# Uc_Ticketing_Slave.net
KiCad netlist of a schematic drawn in Altium Designer
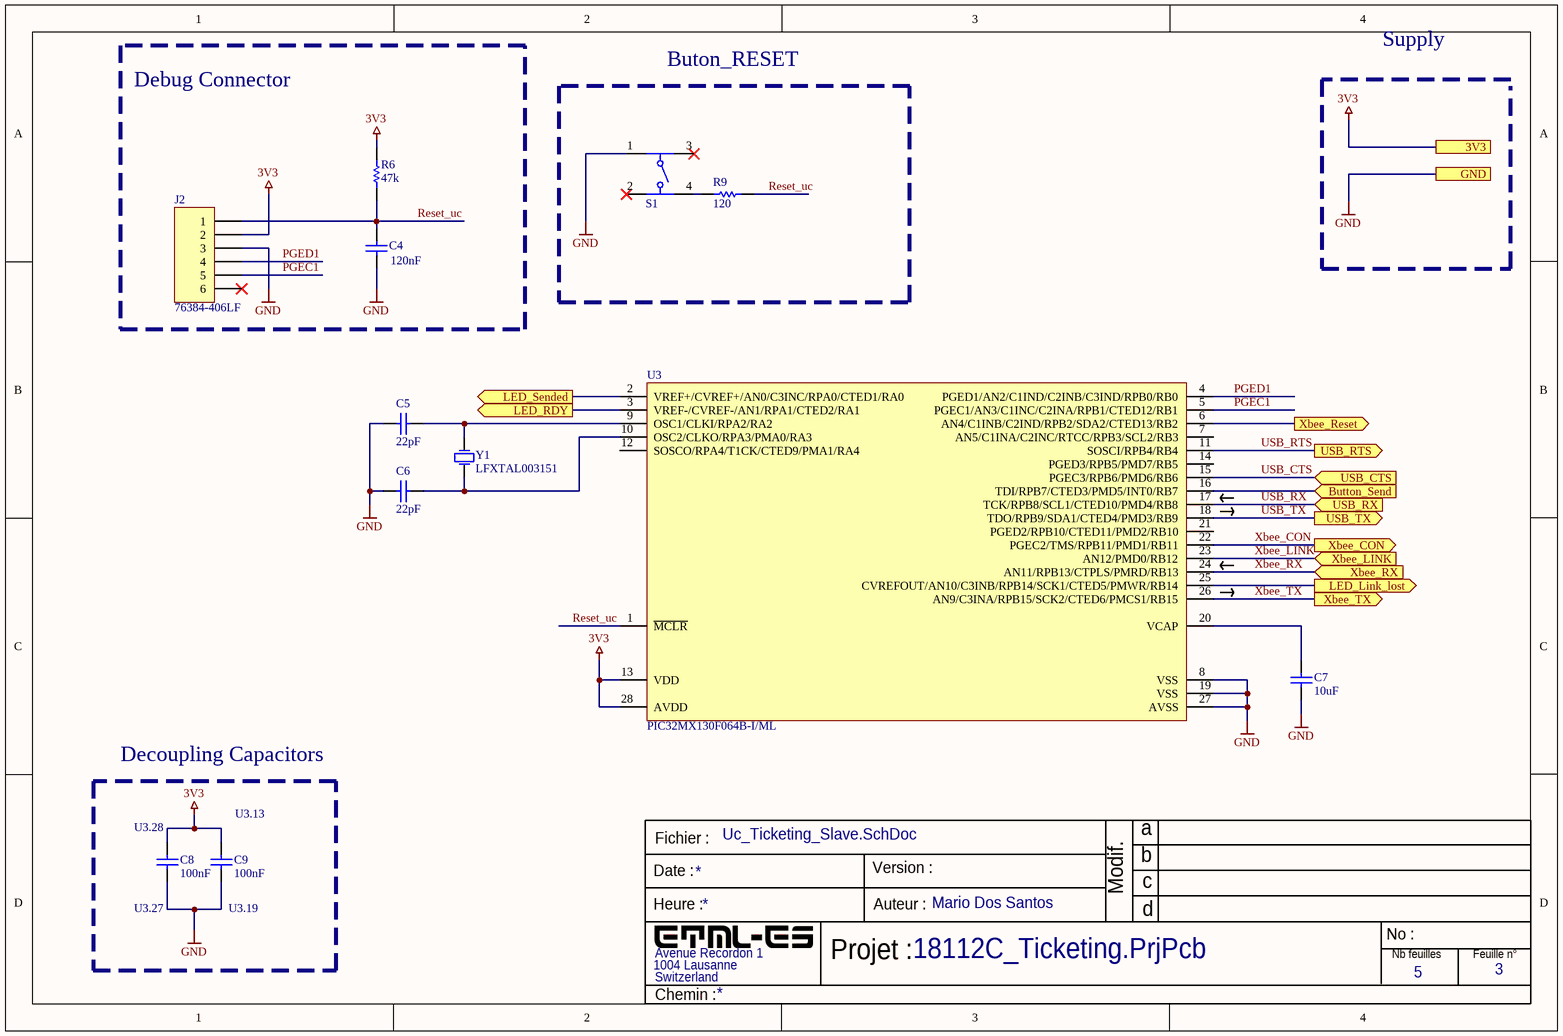
[diagram p0: Uc_Ticketing_Slave.SchDoc]

(export (version "E")
  (design (tool "Eeschema 10.0.6"))
  (components
    (comp (ref "C4")
      (value "120nF")
      (footprint "6-0805_N")
      (description "Capacitor")
      (libsource (lib "Miscellaneous Devices") (part "Cap"))
    )
    (comp (ref "C5")
      (value "22pF")
      (footprint "6-0805_N")
      (description "VJ0805Y104KNAAT")
      (libsource (lib "2126_AffichageMatriciel") (part "CMP-2007-03167-1"))
    )
    (comp (ref "C6")
      (value "22pF")
      (footprint "6-0805_N")
      (description "VJ0805Y104KNAAT")
      (libsource (lib "2126_AffichageMatriciel") (part "CMP-2007-03167-1"))
    )
    (comp (ref "C7")
      (value "10uF")
      (footprint "6-0805_N")
      (description "Capacitor")
      (libsource (lib "Miscellaneous Devices") (part "Cap"))
    )
    (comp (ref "C8")
      (value "100nF")
      (footprint "6-0805_N")
      (description "Capacitor")
      (libsource (lib "Miscellaneous Devices") (part "Cap"))
    )
    (comp (ref "C9")
      (value "100nF")
      (footprint "6-0805_N")
      (description "Capacitor")
      (libsource (lib "Miscellaneous Devices") (part "Cap"))
    )
    (comp (ref "J2")
      (value "76384-406LF")
      (footprint "76384-406LF")
      (description "Header, 6-Pin")
      (fields (field (name "PUBLISHER") "Altium Limited"))
      (libsource (lib "Miscellaneous Connectors") (part "Header 6"))
    )
    (comp (ref "R6")
      (value "47k")
      (footprint "RESC0805(2012)_L")
      (description "100K 0.125W 5% 0805 (2012 Metric)  SMD")
      (libsource (lib "Altium Content Vault") (part "CMP-1013-00122-1"))
    )
    (comp (ref "R9")
      (value "120")
      (footprint "RESC0805(2012)_L")
      (description "100K 0.125W 5% 0805 (2012 Metric)  SMD")
      (libsource (lib "Altium Content Vault") (part "CMP-1013-00122-1"))
    )
    (comp (ref "S1")
      (value "430182050816")
      (footprint "430182050816")
      (description "6x6mm SMD Tact Switch WS-TASV, height 5 mm, 160 gf")
      (libsource (lib "ALTIUM-WS-TASV-rev17b") (part "430182050816"))
    )
    (comp (ref "U3")
      (value "PIC32MX130F064B-I/ML")
      (footprint "SOP65P780X200-28N")
      (libsource (lib "PCB_Ticketing_Slave") (part "CMP-0048-00437-1"))
    )
    (comp (ref "Y1")
      (value "LFXTAL003151")
      (footprint "LFXTAL003151REEL")
      (description "Crystal or Oscillator")
      (libsource (lib "2126_AffichageMatriciel") (part "LFXTAL003151REEL"))
    )
  )
  (nets
    (net (code "1") (name "/Button_Send") (class "Default")
      (node (ref "U3") (pin "16") (pinfunction "TDI/RPB7/CTED3/PMD5/INT0/RB7_16") (pintype "passive"))
    )
    (net (code "2") (name "/LED_Link_lost") (class "Default")
      (node (ref "U3") (pin "25") (pinfunction "CVREFOUT/AN10/C3INB/RPB14/SCK1/CTED5/PMWR/RB14_25") (pintype "passive"))
    )
    (net (code "3") (name "/LED_RDY") (class "Default")
      (node (ref "U3") (pin "3") (pinfunction "VREF-/CVREF-/AN1/RPA1/CTED2/RA1_3") (pintype "passive"))
    )
    (net (code "4") (name "/LED_Sended") (class "Default")
      (node (ref "U3") (pin "2") (pinfunction "VREF+/CVREF+/AN0/C3INC/RPA0/CTED1/RA0_2") (pintype "passive"))
    )
    (net (code "5") (name "/PGEC1") (class "Default")
      (node (ref "J2") (pin "5") (pinfunction "5_5") (pintype "passive"))
      (node (ref "U3") (pin "5") (pinfunction "PGEC1/AN3/C1INC/C2INA/RPB1/CTED12/RB1_5") (pintype "passive"))
    )
    (net (code "6") (name "/PGED1") (class "Default")
      (node (ref "J2") (pin "4") (pinfunction "4_4") (pintype "passive"))
      (node (ref "U3") (pin "4") (pinfunction "PGED1/AN2/C1IND/C2INB/C3IND/RPB0/RB0_4") (pintype "passive"))
    )
    (net (code "7") (name "/Reset_uc") (class "Default")
      (node (ref "C4") (pin "2") (pinfunction "2_2") (pintype "passive"))
      (node (ref "J2") (pin "1") (pinfunction "1_1") (pintype "passive"))
      (node (ref "R6") (pin "2") (pinfunction "2_2") (pintype "passive"))
      (node (ref "R9") (pin "2") (pinfunction "2_2") (pintype "passive"))
      (node (ref "U3") (pin "1") (pinfunction "~{MCLR}_1") (pintype "passive"))
    )
    (net (code "8") (name "/USB_CTS") (class "Default")
      (node (ref "U3") (pin "15") (pinfunction "PGEC3/RPB6/PMD6/RB6_15") (pintype "passive"))
    )
    (net (code "9") (name "/USB_RTS") (class "Default")
      (node (ref "U3") (pin "11") (pinfunction "SOSCI/RPB4/RB4_11") (pintype "passive"))
    )
    (net (code "10") (name "/USB_RX") (class "Default")
      (node (ref "U3") (pin "17") (pinfunction "TCK/RPB8/SCL1/CTED10/PMD4/RB8_17") (pintype "passive"))
    )
    (net (code "11") (name "/USB_TX") (class "Default")
      (node (ref "U3") (pin "18") (pinfunction "TDO/RPB9/SDA1/CTED4/PMD3/RB9_18") (pintype "passive"))
    )
    (net (code "12") (name "/Xbee_CON") (class "Default")
      (node (ref "U3") (pin "22") (pinfunction "PGEC2/TMS/RPB11/PMD1/RB11_22") (pintype "passive"))
    )
    (net (code "13") (name "/Xbee_LINK") (class "Default")
      (node (ref "U3") (pin "23") (pinfunction "AN12/PMD0/RB12_23") (pintype "passive"))
    )
    (net (code "14") (name "/Xbee_RX") (class "Default")
      (node (ref "U3") (pin "24") (pinfunction "AN11/RPB13/CTPLS/PMRD/RB13_24") (pintype "passive"))
    )
    (net (code "15") (name "/Xbee_Reset") (class "Default")
      (node (ref "U3") (pin "6") (pinfunction "AN4/C1INB/C2IND/RPB2/SDA2/CTED13/RB2_6") (pintype "passive"))
    )
    (net (code "16") (name "/Xbee_TX") (class "Default")
      (node (ref "U3") (pin "26") (pinfunction "AN9/C3INA/RPB15/SCK2/CTED6/PMCS1/RB15_26") (pintype "passive"))
    )
    (net (code "17") (name "3V3") (class "Default")
      (node (ref "C8") (pin "2") (pinfunction "2_2") (pintype "passive"))
      (node (ref "C9") (pin "2") (pinfunction "2_2") (pintype "passive"))
      (node (ref "J2") (pin "2") (pinfunction "2_2") (pintype "passive"))
      (node (ref "R6") (pin "1") (pinfunction "1_1") (pintype "passive"))
      (node (ref "U3") (pin "13") (pinfunction "VDD_13") (pintype "passive"))
      (node (ref "U3") (pin "28") (pinfunction "AVDD_28") (pintype "passive"))
    )
    (net (code "18") (name "GND") (class "Default")
      (node (ref "C4") (pin "1") (pinfunction "1_1") (pintype "passive"))
      (node (ref "C5") (pin "1") (pinfunction "1_1") (pintype "passive"))
      (node (ref "C6") (pin "1") (pinfunction "1_1") (pintype "passive"))
      (node (ref "C7") (pin "1") (pinfunction "1_1") (pintype "passive"))
      (node (ref "C8") (pin "1") (pinfunction "1_1") (pintype "passive"))
      (node (ref "C9") (pin "1") (pinfunction "1_1") (pintype "passive"))
      (node (ref "J2") (pin "3") (pinfunction "3_3") (pintype "passive"))
      (node (ref "S1") (pin "1") (pinfunction "1_1") (pintype "passive"))
      (node (ref "U3") (pin "19") (pinfunction "VSS_19") (pintype "passive"))
      (node (ref "U3") (pin "27") (pinfunction "AVSS_27") (pintype "passive"))
      (node (ref "U3") (pin "8") (pinfunction "VSS_8") (pintype "passive"))
    )
    (net (code "19") (name "Net-(R9-Pad1)") (class "Default")
      (node (ref "R9") (pin "1") (pinfunction "1_1") (pintype "passive"))
      (node (ref "S1") (pin "4") (pinfunction "4_4") (pintype "passive"))
    )
    (net (code "20") (name "Net-(U3-OSC1{slash}CLKI{slash}RPA2{slash}RA2)") (class "Default")
      (node (ref "C5") (pin "2") (pinfunction "2_2") (pintype "passive"))
      (node (ref "U3") (pin "9") (pinfunction "OSC1/CLKI/RPA2/RA2_9") (pintype "passive"))
      (node (ref "Y1") (pin "1") (pinfunction "1_1") (pintype "passive"))
    )
    (net (code "21") (name "Net-(U3-OSC2{slash}CLKO{slash}RPA3{slash}PMA0{slash}RA3)") (class "Default")
      (node (ref "C6") (pin "2") (pinfunction "2_2") (pintype "passive"))
      (node (ref "U3") (pin "10") (pinfunction "OSC2/CLKO/RPA3/PMA0/RA3_10") (pintype "passive"))
      (node (ref "Y1") (pin "2") (pinfunction "2_2") (pintype "passive"))
    )
    (net (code "22") (name "Net-(U3-VCAP)") (class "Default")
      (node (ref "C7") (pin "2") (pinfunction "2_2") (pintype "passive"))
      (node (ref "U3") (pin "20") (pinfunction "VCAP_20") (pintype "passive"))
    )
    (net (code "23") (name "unconnected-(J2-Pad6)") (class "Default")
      (node (ref "J2") (pin "6") (pinfunction "6_6") (pintype "passive+no_connect"))
    )
    (net (code "24") (name "unconnected-(S1-Pad2)") (class "Default")
      (node (ref "S1") (pin "2") (pinfunction "2_2") (pintype "passive+no_connect"))
    )
    (net (code "25") (name "unconnected-(S1-Pad3)") (class "Default")
      (node (ref "S1") (pin "3") (pinfunction "3_3") (pintype "passive+no_connect"))
    )
    (net (code "26") (name "unconnected-(U3-AN5{slash}C1INA{slash}C2INC{slash}RTCC{slash}RPB3{slash}SCL2{slash}RB3-Pad7)") (class "Default")
      (node (ref "U3") (pin "7") (pinfunction "AN5/C1INA/C2INC/RTCC/RPB3/SCL2/RB3_7") (pintype "passive"))
    )
    (net (code "27") (name "unconnected-(U3-PGED2{slash}RPB10{slash}CTED11{slash}PMD2{slash}RB10-Pad21)") (class "Default")
      (node (ref "U3") (pin "21") (pinfunction "PGED2/RPB10/CTED11/PMD2/RB10_21") (pintype "passive"))
    )
    (net (code "28") (name "unconnected-(U3-PGED3{slash}RPB5{slash}PMD7{slash}RB5-Pad14)") (class "Default")
      (node (ref "U3") (pin "14") (pinfunction "PGED3/RPB5/PMD7/RB5_14") (pintype "passive"))
    )
    (net (code "29") (name "unconnected-(U3-SOSCO{slash}RPA4{slash}T1CK{slash}CTED9{slash}PMA1{slash}RA4-Pad12)") (class "Default")
      (node (ref "U3") (pin "12") (pinfunction "SOSCO/RPA4/T1CK/CTED9/PMA1/RA4_12") (pintype "passive"))
    )
  )
)
